# Audio.net
KiCad netlist of a schematic drawn in Altium Designer
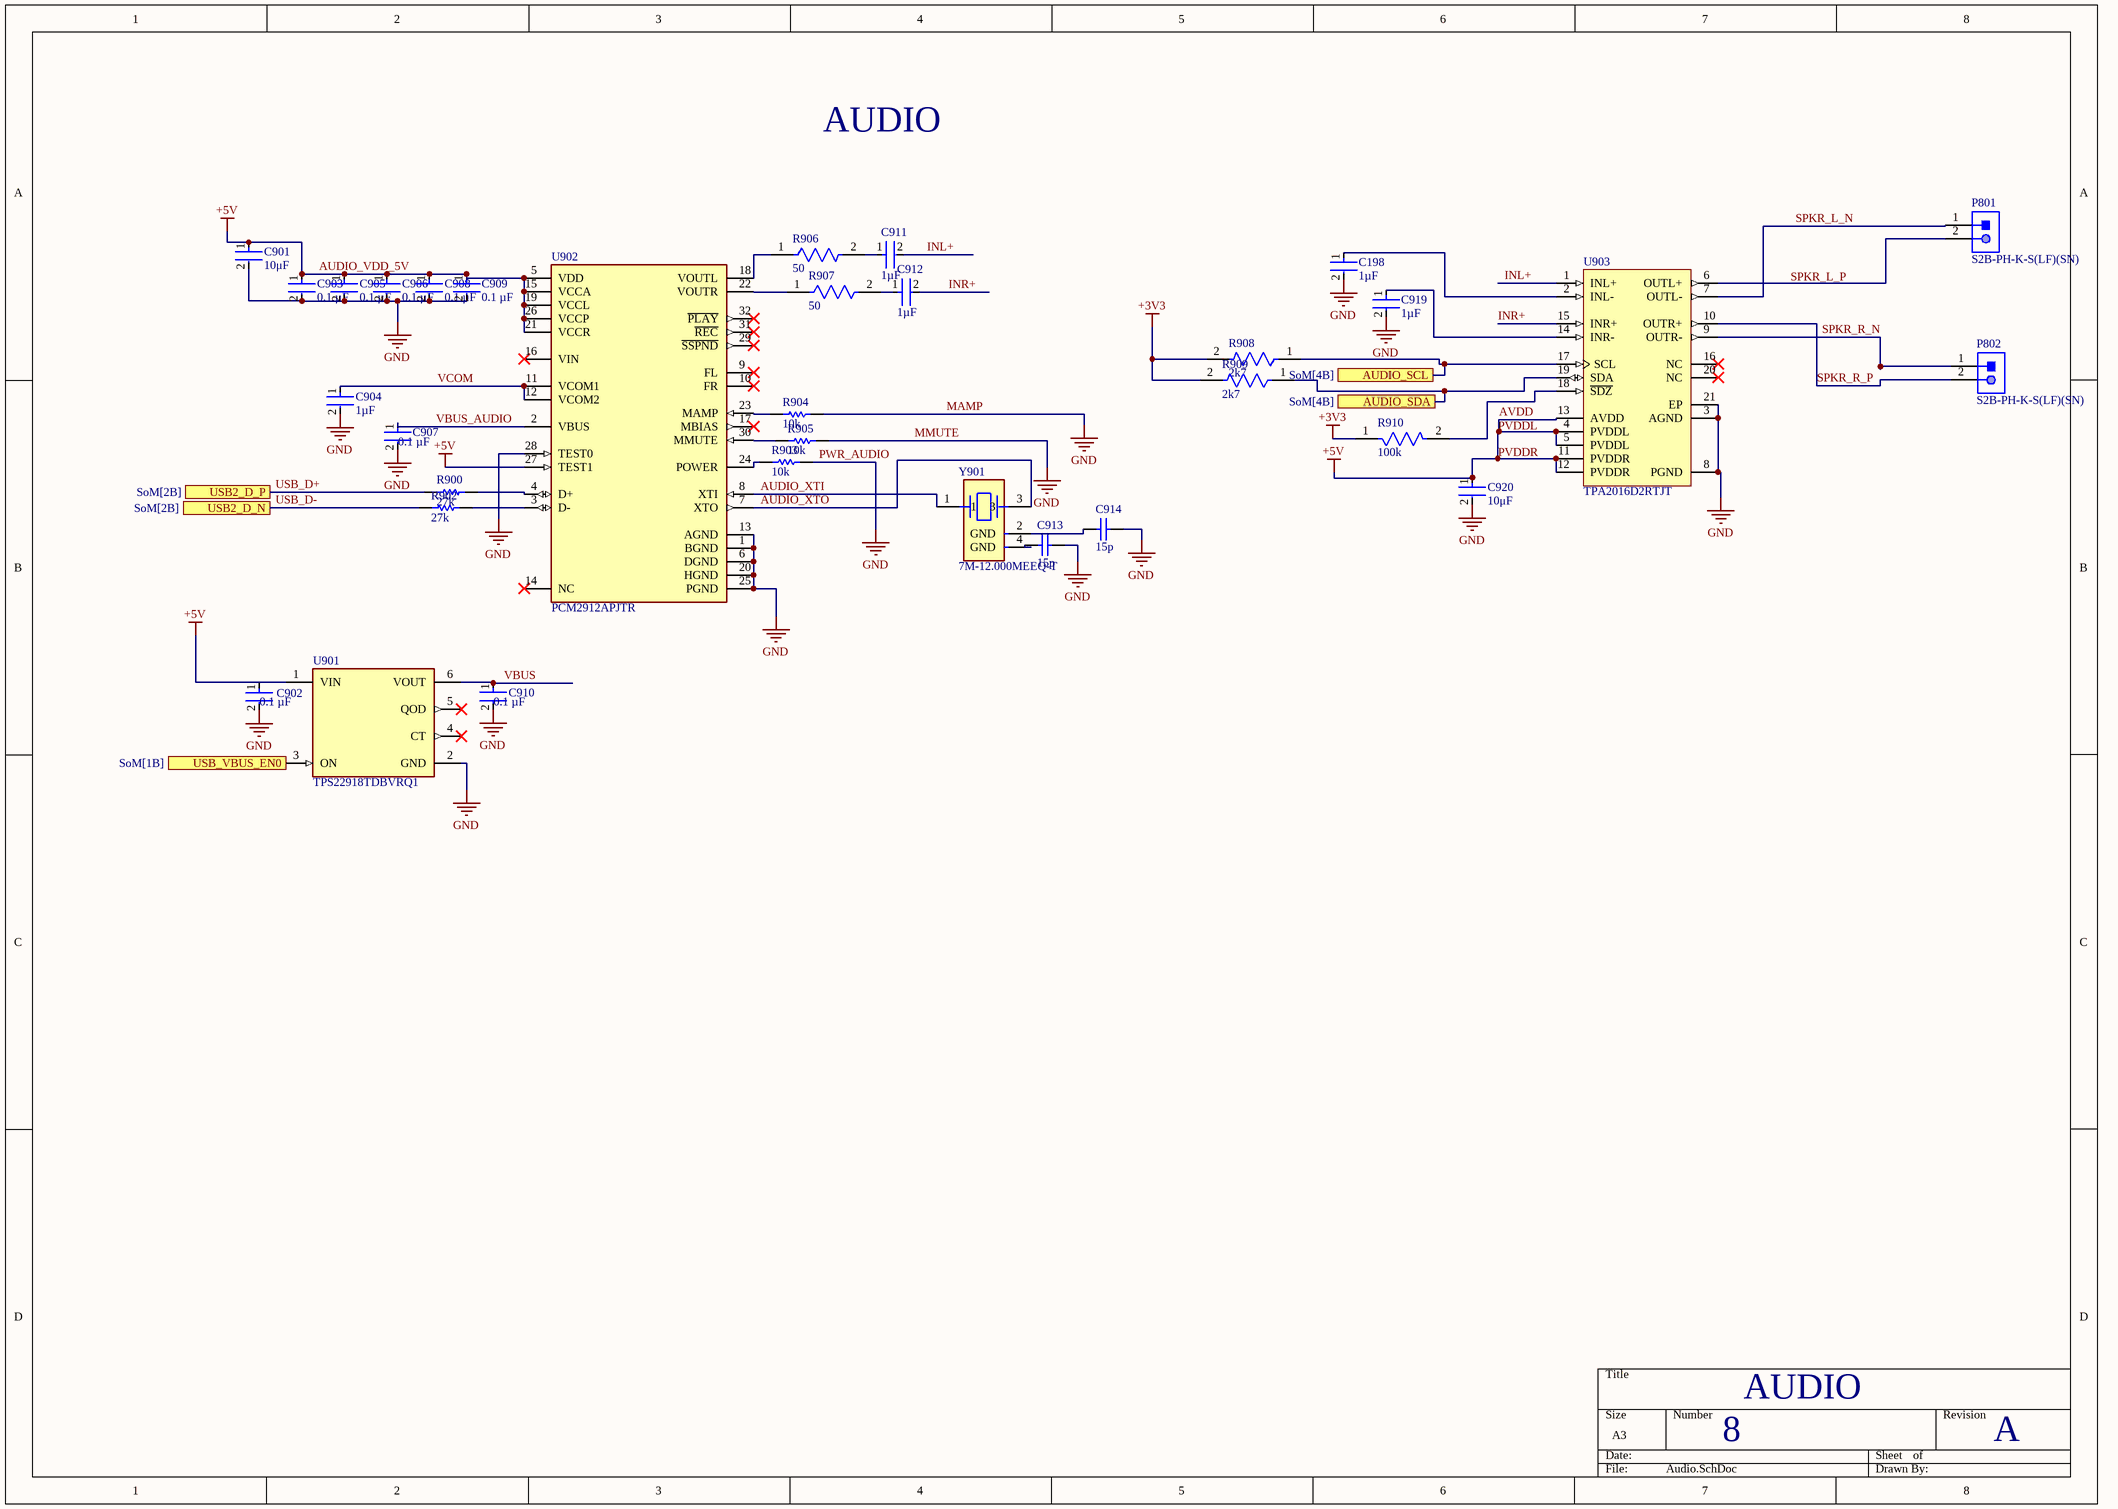
[diagram p0: Audio.SchDoc]

(export (version "E")
  (design (tool "Eeschema 10.0.6"))
  (components
    (comp (ref "C198")
      (value "1µF")
      (footprint "FP-GRM15-0_1-MFG")
      (description "CAP CER 1UF 10V X5R 0402")
      (fields
        (field (name "OCTOPART") "https://octopart.com/grm155r61a105ke15d-murata-197442")
        (field (name "MANUFACTURER PART NUMBER") "GRM155R61A105KE15D")
      )
      (libsource (lib "Altium Content Vault") (part "02cd4be3c70576c341d710602a673aa"))
    )
    (comp (ref "C901")
      (value "10μF")
      (footprint "FP-GRM31C-0_2-e0_3_0_8-MFG")
      (description "Chip Multilayer Ceramic Capacitors for General Purpose, 1206, 10uF, X7R, 15%, 10%, 25V")
      (fields (field (name "TOLERANCE") "10%") (field (name "VOLTAGE") "25V"))
      (libsource (lib "Altium Content Vault") (part "02cd4be3c70576c341d710602a673aa"))
    )
    (comp (ref "C902")
      (value "0.1 µF")
      (footprint "FP-GRM155-0_05-IPC_B")
      (description "Chip Multilayer Ceramic Capacitors for General Purpose, 0402, 0.10uF, X7R, 15%, 10%, 50V")
      (fields (field (name "TOLERANCE") "10%"))
      (libsource (lib "Altium Content Vault") (part "02cd4be3c70576c341d710602a673aa"))
    )
    (comp (ref "C903")
      (value "0.1 µF")
      (footprint "FP-GRM155-0_05-IPC_B")
      (description "Chip Multilayer Ceramic Capacitors for General Purpose, 0402, 0.10uF, X7R, 15%, 10%, 50V")
      (fields (field (name "TOLERANCE") "10%"))
      (libsource (lib "Altium Content Vault") (part "02cd4be3c70576c341d710602a673aa"))
    )
    (comp (ref "C904")
      (value "1µF")
      (footprint "FP-GRM15-0_1-MFG")
      (description "CAP CER 1UF 10V X5R 0402")
      (fields
        (field (name "OCTOPART") "https://octopart.com/grm155r61a105ke15d-murata-197442")
        (field (name "MANUFACTURER PART NUMBER") "GRM155R61A105KE15D")
      )
      (libsource (lib "Altium Content Vault") (part "02cd4be3c70576c341d710602a673aa"))
    )
    (comp (ref "C905")
      (value "0.1 µF")
      (footprint "FP-GRM155-0_05-IPC_B")
      (description "Chip Multilayer Ceramic Capacitors for General Purpose, 0402, 0.10uF, X7R, 15%, 10%, 50V")
      (fields (field (name "TOLERANCE") "10%"))
      (libsource (lib "Altium Content Vault") (part "02cd4be3c70576c341d710602a673aa"))
    )
    (comp (ref "C906")
      (value "0.1 µF")
      (footprint "FP-GRM155-0_05-IPC_B")
      (description "Chip Multilayer Ceramic Capacitors for General Purpose, 0402, 0.10uF, X7R, 15%, 10%, 50V")
      (fields (field (name "TOLERANCE") "10%"))
      (libsource (lib "Altium Content Vault") (part "02cd4be3c70576c341d710602a673aa"))
    )
    (comp (ref "C907")
      (value "0.1 µF")
      (footprint "FP-GRM155-0_05-IPC_B")
      (description "Chip Multilayer Ceramic Capacitors for General Purpose, 0402, 0.10uF, X7R, 15%, 10%, 50V")
      (fields (field (name "TOLERANCE") "10%"))
      (libsource (lib "Altium Content Vault") (part "02cd4be3c70576c341d710602a673aa"))
    )
    (comp (ref "C908")
      (value "0.1 µF")
      (footprint "FP-GRM155-0_05-IPC_B")
      (description "Chip Multilayer Ceramic Capacitors for General Purpose, 0402, 0.10uF, X7R, 15%, 10%, 50V")
      (fields (field (name "TOLERANCE") "10%"))
      (libsource (lib "Altium Content Vault") (part "02cd4be3c70576c341d710602a673aa"))
    )
    (comp (ref "C909")
      (value "0.1 µF")
      (footprint "FP-GRM155-0_05-IPC_B")
      (description "Chip Multilayer Ceramic Capacitors for General Purpose, 0402, 0.10uF, X7R, 15%, 10%, 50V")
      (fields (field (name "TOLERANCE") "10%"))
      (libsource (lib "Altium Content Vault") (part "02cd4be3c70576c341d710602a673aa"))
    )
    (comp (ref "C910")
      (value "0.1 µF")
      (footprint "FP-GRM155-0_05-IPC_B")
      (description "Chip Multilayer Ceramic Capacitors for General Purpose, 0402, 0.10uF, X7R, 15%, 10%, 50V")
      (fields (field (name "TOLERANCE") "10%"))
      (libsource (lib "Altium Content Vault") (part "02cd4be3c70576c341d710602a673aa"))
    )
    (comp (ref "C911")
      (value "1µF")
      (footprint "FP-GRM15-0_1-MFG")
      (description "CAP CER 1UF 10V X5R 0402")
      (fields
        (field (name "OCTOPART") "https://octopart.com/grm155r61a105ke15d-murata-197442")
        (field (name "MANUFACTURER PART NUMBER") "GRM155R61A105KE15D")
      )
      (libsource (lib "Altium Content Vault") (part "02cd4be3c70576c341d710602a673aa"))
    )
    (comp (ref "C912")
      (value "1µF")
      (footprint "FP-GRM15-0_1-MFG")
      (description "CAP CER 1UF 10V X5R 0402")
      (fields
        (field (name "OCTOPART") "https://octopart.com/grm155r61a105ke15d-murata-197442")
        (field (name "MANUFACTURER PART NUMBER") "GRM155R61A105KE15D")
      )
      (libsource (lib "Altium Content Vault") (part "02cd4be3c70576c341d710602a673aa"))
    )
    (comp (ref "C913")
      (value "15p")
      (footprint "CAPC1005X55X25LL05T10")
      (fields (field (name "MANUFACTURER") "Murata") (field (name "PART NUMBER") "GRM1555C1H150JA01D"))
      (libsource (lib "Altium Content Vault") (part "CAP"))
    )
    (comp (ref "C914")
      (value "15p")
      (footprint "CAPC1005X55X25LL05T10")
      (fields (field (name "MANUFACTURER") "Murata") (field (name "PART NUMBER") "GRM1555C1H150JA01D"))
      (libsource (lib "Altium Content Vault") (part "CAP"))
    )
    (comp (ref "C919")
      (value "1µF")
      (footprint "FP-GRM15-0_1-MFG")
      (description "CAP CER 1UF 10V X5R 0402")
      (fields
        (field (name "OCTOPART") "https://octopart.com/grm155r61a105ke15d-murata-197442")
        (field (name "MANUFACTURER PART NUMBER") "GRM155R61A105KE15D")
      )
      (libsource (lib "Altium Content Vault") (part "02cd4be3c70576c341d710602a673aa"))
    )
    (comp (ref "C920")
      (value "10μF")
      (footprint "FP-GRM31C-0_2-e0_3_0_8-MFG")
      (description "Chip Multilayer Ceramic Capacitors for General Purpose, 1206, 10uF, X7R, 15%, 10%, 25V")
      (fields (field (name "TOLERANCE") "10%") (field (name "VOLTAGE") "25V"))
      (libsource (lib "Altium Content Vault") (part "02cd4be3c70576c341d710602a673aa"))
    )
    (comp (ref "P801")
      (value "S2B-PH-K-S(LF)(SN)")
      (footprint "JST-S2B-PH-K-S_V")
      (fields (field (name "TOLERANCE") "20%"))
      (libsource (lib "Altium Content Vault") (part "CN-1P-M-R2"))
    )
    (comp (ref "P802")
      (value "S2B-PH-K-S(LF)(SN)")
      (footprint "JST-S2B-PH-K-S_V")
      (fields (field (name "TOLERANCE") "20%"))
      (libsource (lib "Altium Content Vault") (part "CN-1P-M-R2"))
    )
    (comp (ref "R900")
      (value "27k")
      (footprint "RESC1005X40X25LL05T10")
      (fields (field (name "PART NUMBER") "RC0402FR-0727RL") (field (name "MANUFACTURER") "Yageo / Phycomp"))
      (libsource (lib "Altium Content Vault") (part "RES"))
    )
    (comp (ref "R902")
      (value "27k")
      (footprint "RESC1005X40X25LL05T10")
      (fields (field (name "PART NUMBER") "RC0402FR-0727RL") (field (name "MANUFACTURER") "Yageo / Phycomp"))
      (libsource (lib "Altium Content Vault") (part "RES"))
    )
    (comp (ref "R903")
      (value "10k")
      (footprint "RESC1005X40X25LL05T10")
      (fields (field (name "PART NUMBER") "RC0402FR-0710KL") (field (name "MANUFACTURER") "Yageo / Phycomp"))
      (libsource (lib "Altium Content Vault") (part "RES"))
    )
    (comp (ref "R904")
      (value "10k")
      (footprint "RESC1005X40X25LL05T10")
      (fields (field (name "PART NUMBER") "RC0402FR-0710KL") (field (name "MANUFACTURER") "Yageo / Phycomp"))
      (libsource (lib "Altium Content Vault") (part "RES"))
    )
    (comp (ref "R905")
      (value "10k")
      (footprint "RESC1005X40X25LL05T10")
      (fields (field (name "PART NUMBER") "RC0402FR-0710KL") (field (name "MANUFACTURER") "Yageo / Phycomp"))
      (libsource (lib "Altium Content Vault") (part "RES"))
    )
    (comp (ref "R906")
      (value "50")
      (footprint "FP-CRCW0603-e3-MFG")
      (description "RES Thick Film, 50Ω, 1%, 0.1W, 100ppm/°C, 0603")
      (fields (field (name "TOLERANCE") "1%"))
      (libsource (lib "Altium Content Vault") (part "1029c3af85768c4190bb7ad29bc67b5"))
    )
    (comp (ref "R907")
      (value "50")
      (footprint "FP-CRCW0603-e3-MFG")
      (description "RES Thick Film, 50Ω, 1%, 0.1W, 100ppm/°C, 0603")
      (fields (field (name "TOLERANCE") "1%"))
      (libsource (lib "Altium Content Vault") (part "1029c3af85768c4190bb7ad29bc67b5"))
    )
    (comp (ref "R908")
      (value "2k7")
      (footprint "FP-CR0402-IPC_B")
      (description "Thick Film Chip Resistors 0402 2.7kΩ 0.0625W 1% 100ppm/°C")
      (fields (field (name "TOLERANCE") "1%"))
      (libsource (lib "Altium Content Vault") (part "1029c3af85768c4190bb7ad29bc67b5"))
    )
    (comp (ref "R909")
      (value "2k7")
      (footprint "FP-CR0402-IPC_B")
      (description "Thick Film Chip Resistors 0402 2.7kΩ 0.0625W 1% 100ppm/°C")
      (fields (field (name "TOLERANCE") "1%"))
      (libsource (lib "Altium Content Vault") (part "1029c3af85768c4190bb7ad29bc67b5"))
    )
    (comp (ref "R910")
      (value "100k")
      (footprint "FP-RC0402-0_4-IPC_A")
      (description "RES 100K OHM 5% 1/16W 0402")
      (fields (field (name "TOLERANCE") "5%"))
      (libsource (lib "Altium Content Vault") (part "1029c3af85768c4190bb7ad29bc67b5"))
    )
    (comp (ref "U901")
      (value "TPS22918TDBVRQ1")
      (footprint "FP-DBV0006A-IPC_C")
      (description "IC PWR SWITCH N-CHAN 1:1 SOT23-6")
      (libsource (lib "Altium Content Vault") (part "8b1f3cf37ce29d5f7477cf0fde67f53"))
    )
    (comp (ref "U902")
      (value "PCM2912APJTR")
      (footprint "FP-PJT0032A-IPC_C")
      (description "IC STEREO AUD CODEC W/USB 32TQFP")
      (libsource (lib "Altium Content Vault") (part "253ddf6499021ded57be087bdc4fbd2"))
    )
    (comp (ref "U903")
      (value "TPA2016D2RTJT")
      (footprint "RTJ0020D_V")
      (fields (field (name "MANUFACTURER") "Texas Instruments"))
      (libsource (lib "Altium Content Vault") (part "TI-TPA2016D2RTJ20-2700X2700TP"))
    )
    (comp (ref "Y901")
      (value "7M-12.000MEEQ-T")
      (footprint "FP-7M-MFG")
      (description "Crystal 12MHz, 10ppm, 10pF, 80Ω")
      (fields (field (name "TOLERANCE") "10ppm"))
      (libsource (lib "Altium Content Vault") (part "41079aabb0e87794b56622915be14ed"))
    )
  )
  (nets
    (net (code "1") (name "+3V3") (class "Default")
      (node (ref "R908") (pin "2") (pinfunction "2_2") (pintype "passive"))
      (node (ref "R909") (pin "2") (pinfunction "2_2") (pintype "passive"))
      (node (ref "R910") (pin "1") (pinfunction "1_1") (pintype "passive"))
    )
    (net (code "2") (name "+5V") (class "Default")
      (node (ref "C901") (pin "1") (pinfunction "1_1") (pintype "passive"))
      (node (ref "C903") (pin "1") (pinfunction "1_1") (pintype "passive"))
      (node (ref "C905") (pin "1") (pinfunction "1_1") (pintype "passive"))
      (node (ref "C906") (pin "1") (pinfunction "1_1") (pintype "passive"))
      (node (ref "C908") (pin "1") (pinfunction "1_1") (pintype "passive"))
      (node (ref "C909") (pin "1") (pinfunction "1_1") (pintype "passive"))
      (node (ref "C920") (pin "1") (pinfunction "1_1") (pintype "passive"))
      (node (ref "U901") (pin "1") (pinfunction "VIN_1") (pintype "power_in"))
      (node (ref "U902") (pin "15") (pinfunction "VCCA_15") (pintype "power_in"))
      (node (ref "U902") (pin "19") (pinfunction "VCCL_19") (pintype "power_in"))
      (node (ref "U902") (pin "21") (pinfunction "VCCR_21") (pintype "power_in"))
      (node (ref "U902") (pin "26") (pinfunction "VCCP_26") (pintype "power_in"))
      (node (ref "U902") (pin "27") (pinfunction "TEST1_27") (pintype "input"))
      (node (ref "U902") (pin "5") (pinfunction "VDD_5") (pintype "power_in"))
      (node (ref "U903") (pin "11") (pinfunction "PVDDR_11") (pintype "power_in"))
      (node (ref "U903") (pin "12") (pinfunction "PVDDR_12") (pintype "power_in"))
      (node (ref "U903") (pin "13") (pinfunction "AVDD_13") (pintype "power_in"))
      (node (ref "U903") (pin "4") (pinfunction "PVDDL_4") (pintype "power_in"))
      (node (ref "U903") (pin "5") (pinfunction "PVDDL_5") (pintype "power_in"))
    )
    (net (code "3") (name "/AUDIO_SCL") (class "Default")
      (node (ref "R908") (pin "1") (pinfunction "1_1") (pintype "passive"))
      (node (ref "U903") (pin "17") (pinfunction "SCL_17") (pintype "input"))
    )
    (net (code "4") (name "/AUDIO_SDA") (class "Default")
      (node (ref "R909") (pin "1") (pinfunction "1_1") (pintype "passive"))
      (node (ref "U903") (pin "19") (pinfunction "SDA_19") (pintype "bidirectional"))
    )
    (net (code "5") (name "/AUDIO_XTI") (class "Default")
      (node (ref "U902") (pin "8") (pinfunction "XTI_8") (pintype "input"))
      (node (ref "Y901") (pin "1") (pinfunction "1_1") (pintype "passive"))
    )
    (net (code "6") (name "/AUDIO_XTO") (class "Default")
      (node (ref "U902") (pin "7") (pinfunction "XTO_7") (pintype "output"))
      (node (ref "Y901") (pin "3") (pinfunction "3_3") (pintype "passive"))
    )
    (net (code "7") (name "/INL+") (class "Default")
      (node (ref "C911") (pin "2") (pinfunction "2_2") (pintype "passive"))
      (node (ref "U903") (pin "1") (pinfunction "INL+_1") (pintype "input"))
    )
    (net (code "8") (name "/INR+") (class "Default")
      (node (ref "C912") (pin "2") (pinfunction "2_2") (pintype "passive"))
      (node (ref "U903") (pin "15") (pinfunction "INR+_15") (pintype "input"))
    )
    (net (code "9") (name "/SPKR_L_N") (class "Default")
      (node (ref "P801") (pin "1") (pinfunction "1_1") (pintype "passive"))
      (node (ref "U903") (pin "7") (pinfunction "OUTL-_7") (pintype "output"))
    )
    (net (code "11") (name "/SPKR_R_N") (class "Default")
      (node (ref "P802") (pin "1") (pinfunction "1_1") (pintype "passive"))
      (node (ref "U903") (pin "9") (pinfunction "OUTR-_9") (pintype "output"))
    )
    (net (code "12") (name "/SPKR_R_P") (class "Default")
      (node (ref "P802") (pin "2") (pinfunction "2_2") (pintype "passive"))
      (node (ref "U903") (pin "10") (pinfunction "OUTR+_10") (pintype "output"))
    )
    (net (code "14") (name "/USB_D+") (class "Default")
      (node (ref "R900") (pin "1") (pinfunction "1_1") (pintype "passive"))
    )
    (net (code "15") (name "/USB_D-") (class "Default")
      (node (ref "R902") (pin "1") (pinfunction "1_1") (pintype "passive"))
    )
    (net (code "16") (name "/USB_VBUS_EN0") (class "Default")
      (node (ref "U901") (pin "3") (pinfunction "ON_3") (pintype "input"))
    )
    (net (code "17") (name "/VBUS") (class "Default")
      (node (ref "C910") (pin "1") (pinfunction "1_1") (pintype "passive"))
      (node (ref "U901") (pin "6") (pinfunction "VOUT_6") (pintype "power_in"))
    )
    (net (code "18") (name "/VBUS_AUDIO") (class "Default")
      (node (ref "C907") (pin "1") (pinfunction "1_1") (pintype "passive"))
      (node (ref "U902") (pin "2") (pinfunction "VBUS_2") (pintype "power_in"))
    )
    (net (code "19") (name "/VCOM") (class "Default")
      (node (ref "C904") (pin "1") (pinfunction "1_1") (pintype "passive"))
      (node (ref "U902") (pin "11") (pinfunction "VCOM1_11") (pintype "power_in"))
      (node (ref "U902") (pin "12") (pinfunction "VCOM2_12") (pintype "power_in"))
    )
    (net (code "20") (name "GND") (class "Default")
      (node (ref "C198") (pin "2") (pinfunction "2_2") (pintype "passive"))
      (node (ref "C901") (pin "2") (pinfunction "2_2") (pintype "passive"))
      (node (ref "C902") (pin "2") (pinfunction "2_2") (pintype "passive"))
      (node (ref "C903") (pin "2") (pinfunction "2_2") (pintype "passive"))
      (node (ref "C904") (pin "2") (pinfunction "2_2") (pintype "passive"))
      (node (ref "C905") (pin "2") (pinfunction "2_2") (pintype "passive"))
      (node (ref "C906") (pin "2") (pinfunction "2_2") (pintype "passive"))
      (node (ref "C907") (pin "2") (pinfunction "2_2") (pintype "passive"))
      (node (ref "C908") (pin "2") (pinfunction "2_2") (pintype "passive"))
      (node (ref "C909") (pin "2") (pinfunction "2_2") (pintype "passive"))
      (node (ref "C910") (pin "2") (pinfunction "2_2") (pintype "passive"))
      (node (ref "C913") (pin "1") (pinfunction "1_1") (pintype "passive"))
      (node (ref "C914") (pin "1") (pinfunction "1_1") (pintype "passive"))
      (node (ref "C919") (pin "2") (pinfunction "2_2") (pintype "passive"))
      (node (ref "C920") (pin "2") (pinfunction "2_2") (pintype "passive"))
      (node (ref "R903") (pin "1") (pinfunction "1_1") (pintype "passive"))
      (node (ref "R904") (pin "1") (pinfunction "1_1") (pintype "passive"))
      (node (ref "R905") (pin "1") (pinfunction "1_1") (pintype "passive"))
      (node (ref "U901") (pin "2") (pinfunction "GND_2") (pintype "power_in"))
      (node (ref "U902") (pin "1") (pinfunction "BGND_1") (pintype "power_in"))
      (node (ref "U902") (pin "13") (pinfunction "AGND_13") (pintype "power_in"))
      (node (ref "U902") (pin "20") (pinfunction "HGND_20") (pintype "power_in"))
      (node (ref "U902") (pin "25") (pinfunction "PGND_25") (pintype "power_in"))
      (node (ref "U902") (pin "28") (pinfunction "TEST0_28") (pintype "input"))
      (node (ref "U902") (pin "6") (pinfunction "DGND_6") (pintype "power_in"))
      (node (ref "U903") (pin "21") (pinfunction "EP_21") (pintype "passive"))
      (node (ref "U903") (pin "3") (pinfunction "AGND_3") (pintype "power_in"))
      (node (ref "U903") (pin "8") (pinfunction "PGND_8") (pintype "power_in"))
    )
    (net (code "21") (name "Net-(C911-Pad1)") (class "Default")
      (node (ref "C911") (pin "1") (pinfunction "1_1") (pintype "passive"))
      (node (ref "R906") (pin "2") (pinfunction "2_2") (pintype "passive"))
    )
    (net (code "22") (name "Net-(C912-Pad1)") (class "Default")
      (node (ref "C912") (pin "1") (pinfunction "1_1") (pintype "passive"))
      (node (ref "R907") (pin "2") (pinfunction "2_2") (pintype "passive"))
    )
    (net (code "23") (name "Net-(C913-Pad2)") (class "Default")
      (node (ref "C913") (pin "2") (pinfunction "2_2") (pintype "passive"))
      (node (ref "Y901") (pin "4") (pinfunction "GND_4") (pintype "power_in"))
    )
    (net (code "24") (name "Net-(C914-Pad2)") (class "Default")
      (node (ref "C914") (pin "2") (pinfunction "2_2") (pintype "passive"))
      (node (ref "Y901") (pin "2") (pinfunction "GND_2") (pintype "power_in"))
    )
    (net (code "25") (name "Net-(U902-D+)") (class "Default")
      (node (ref "R900") (pin "2") (pinfunction "2_2") (pintype "passive"))
      (node (ref "U902") (pin "4") (pinfunction "D+_4") (pintype "bidirectional"))
    )
    (net (code "26") (name "Net-(U902-D-)") (class "Default")
      (node (ref "R902") (pin "2") (pinfunction "2_2") (pintype "passive"))
      (node (ref "U902") (pin "3") (pinfunction "D-_3") (pintype "bidirectional"))
    )
    (net (code "27") (name "Net-(U902-MAMP)") (class "Default")
      (node (ref "R904") (pin "2") (pinfunction "2_2") (pintype "passive"))
      (node (ref "U902") (pin "23") (pinfunction "MAMP_23") (pintype "input"))
    )
    (net (code "28") (name "Net-(U902-MMUTE)") (class "Default")
      (node (ref "R905") (pin "2") (pinfunction "2_2") (pintype "passive"))
      (node (ref "U902") (pin "30") (pinfunction "MMUTE_30") (pintype "input"))
    )
    (net (code "29") (name "Net-(U902-POWER)") (class "Default")
      (node (ref "R903") (pin "2") (pinfunction "2_2") (pintype "passive"))
      (node (ref "U902") (pin "24") (pinfunction "POWER_24") (pintype "power_in"))
    )
    (net (code "30") (name "Net-(U902-VOUTL)") (class "Default")
      (node (ref "R906") (pin "1") (pinfunction "1_1") (pintype "passive"))
      (node (ref "U902") (pin "18") (pinfunction "VOUTL_18") (pintype "power_in"))
    )
    (net (code "31") (name "Net-(U902-VOUTR)") (class "Default")
      (node (ref "R907") (pin "1") (pinfunction "1_1") (pintype "passive"))
      (node (ref "U902") (pin "22") (pinfunction "VOUTR_22") (pintype "power_in"))
    )
    (net (code "32") (name "Net-(U903-INL-)") (class "Default")
      (node (ref "C198") (pin "1") (pinfunction "1_1") (pintype "passive"))
      (node (ref "U903") (pin "2") (pinfunction "INL-_2") (pintype "input"))
    )
    (net (code "33") (name "Net-(U903-INR-)") (class "Default")
      (node (ref "C919") (pin "1") (pinfunction "1_1") (pintype "passive"))
      (node (ref "U903") (pin "14") (pinfunction "INR-_14") (pintype "input"))
    )
    (net (code "34") (name "Net-(U903-OUTL+)") (class "Default")
      (node (ref "P801") (pin "2") (pinfunction "2_2") (pintype "passive"))
      (node (ref "U903") (pin "6") (pinfunction "OUTL+_6") (pintype "output"))
    )
    (net (code "35") (name "Net-(U903-~{SDZ})") (class "Default")
      (node (ref "R910") (pin "2") (pinfunction "2_2") (pintype "passive"))
      (node (ref "U903") (pin "18") (pinfunction "~{SDZ}_18") (pintype "input"))
    )
    (net (code "36") (name "unconnected-(C902-Pad1)") (class "Default")
      (node (ref "C902") (pin "1") (pinfunction "1_1") (pintype "passive"))
    )
    (net (code "37") (name "unconnected-(U901-CT-Pad4)") (class "Default")
      (node (ref "U901") (pin "4") (pinfunction "CT_4") (pintype "output+no_connect"))
    )
    (net (code "38") (name "unconnected-(U901-QOD-Pad5)") (class "Default")
      (node (ref "U901") (pin "5") (pinfunction "QOD_5") (pintype "output+no_connect"))
    )
    (net (code "39") (name "unconnected-(U902-FL-Pad9)") (class "Default")
      (node (ref "U902") (pin "9") (pinfunction "FL_9") (pintype "passive+no_connect"))
    )
    (net (code "40") (name "unconnected-(U902-FR-Pad10)") (class "Default")
      (node (ref "U902") (pin "10") (pinfunction "FR_10") (pintype "passive+no_connect"))
    )
    (net (code "41") (name "unconnected-(U902-MBIAS-Pad17)") (class "Default")
      (node (ref "U902") (pin "17") (pinfunction "MBIAS_17") (pintype "output+no_connect"))
    )
    (net (code "42") (name "unconnected-(U902-NC-Pad14)") (class "Default")
      (node (ref "U902") (pin "14") (pinfunction "NC_14") (pintype "passive+no_connect"))
    )
    (net (code "43") (name "unconnected-(U902-VIN-Pad16)") (class "Default")
      (node (ref "U902") (pin "16") (pinfunction "VIN_16") (pintype "power_in+no_connect"))
    )
    (net (code "44") (name "unconnected-(U902-~{PLAY}-Pad32)") (class "Default")
      (node (ref "U902") (pin "32") (pinfunction "~{PLAY}_32") (pintype "output+no_connect"))
    )
    (net (code "45") (name "unconnected-(U902-~{REC}-Pad31)") (class "Default")
      (node (ref "U902") (pin "31") (pinfunction "~{REC}_31") (pintype "output+no_connect"))
    )
    (net (code "46") (name "unconnected-(U902-~{SSPND}-Pad29)") (class "Default")
      (node (ref "U902") (pin "29") (pinfunction "~{SSPND}_29") (pintype "output+no_connect"))
    )
    (net (code "47") (name "unconnected-(U903-NC-Pad16)") (class "Default")
      (node (ref "U903") (pin "16") (pinfunction "NC_16") (pintype "passive+no_connect"))
    )
    (net (code "48") (name "unconnected-(U903-NC-Pad20)") (class "Default")
      (node (ref "U903") (pin "20") (pinfunction "NC_20") (pintype "passive+no_connect"))
    )
  )
)
